# 12V_VMOT_SUPPLY.net
KiCad netlist of a schematic drawn in Altium Designer
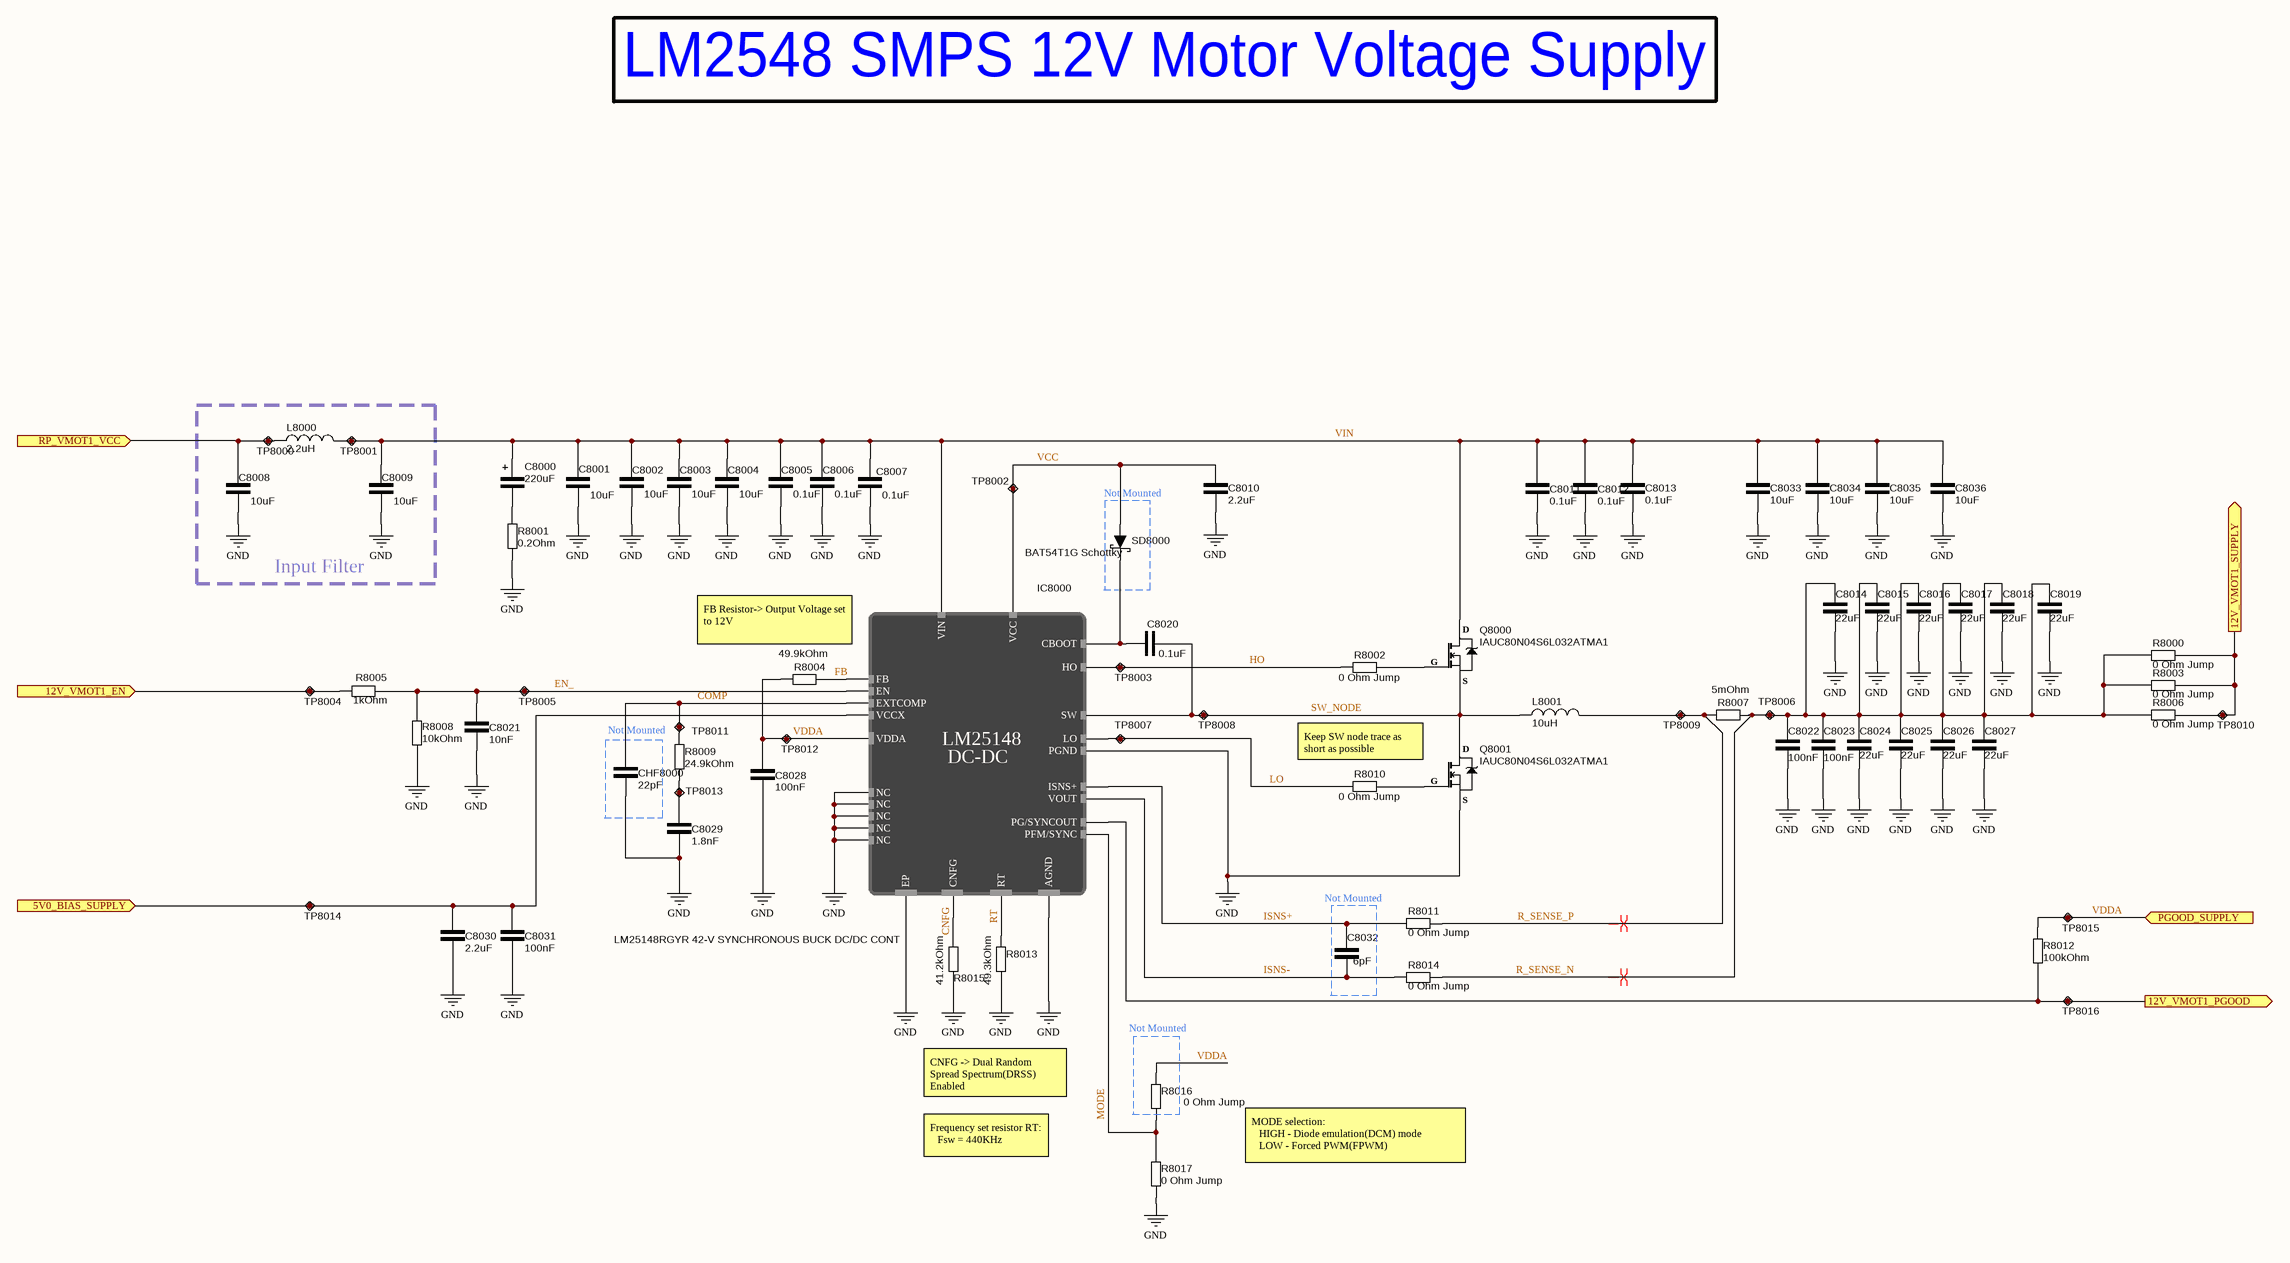
[diagram p0: 12V_VMOT_SUPPLY.SchDoc]

(export (version "E")
  (design (tool "Eeschema 10.0.6"))
  (components
    (comp (ref "C8000")
      (value "220uF")
      (footprint "CAPAE109103X103M")
      (description "220 µF 35 V Aluminum - Polymer Capacitors Radial, Can - SMD 23mOhm 1000 Hrs @ 150°C")
      (fields (field (name "DIGIKEY PART NUMBER") "399-A785MN227M1VLAS023CT-ND"))
      (libsource (lib "CapacitorsIntegrated") (part "C000033"))
    )
    (comp (ref "C8001")
      (value "10uF")
      (footprint "CAP_1206")
      (description "10 µF ±10% 50V Ceramic Capacitor X7R 1206 (3216 Metric)")
      (fields (field (name "DIGIKEY PART NUMBER") "1276-6767-1-ND"))
      (libsource (lib "CapacitorsIntegrated") (part "C000017"))
    )
    (comp (ref "C8002")
      (value "10uF")
      (footprint "CAP_1206")
      (description "10 µF ±10% 50V Ceramic Capacitor X7R 1206 (3216 Metric)")
      (fields (field (name "DIGIKEY PART NUMBER") "1276-6767-1-ND"))
      (libsource (lib "") (part "C000017_1"))
    )
    (comp (ref "C8003")
      (value "10uF")
      (footprint "CAP_1206")
      (description "10 µF ±10% 50V Ceramic Capacitor X7R 1206 (3216 Metric)")
      (fields (field (name "DIGIKEY PART NUMBER") "1276-6767-1-ND"))
      (libsource (lib "") (part "C000017_1"))
    )
    (comp (ref "C8004")
      (value "10uF")
      (footprint "CAP_1206")
      (description "10 µF ±10% 50V Ceramic Capacitor X7R 1206 (3216 Metric)")
      (fields (field (name "DIGIKEY PART NUMBER") "1276-6767-1-ND"))
      (libsource (lib "") (part "C000017_1"))
    )
    (comp (ref "C8005")
      (value "0.1uF")
      (footprint "CAP_0603")
      (description "0.1 µF ±10% 50V Ceramic Capacitor X7R 0603 (1608 Metric)")
      (fields (field (name "DIGIKEY PART NUMBER") "1276-1000-1-ND"))
      (libsource (lib "CapacitorsIntegrated") (part "C000018"))
    )
    (comp (ref "C8006")
      (value "0.1uF")
      (footprint "CAP_0603")
      (description "0.1 µF ±10% 50V Ceramic Capacitor X7R 0603 (1608 Metric)")
      (fields (field (name "DIGIKEY PART NUMBER") "1276-1000-1-ND"))
      (libsource (lib "CapacitorsIntegrated") (part "C000018"))
    )
    (comp (ref "C8007")
      (value "0.1uF")
      (footprint "CAP_0603")
      (description "0.1 µF ±10% 50V Ceramic Capacitor X7R 0603 (1608 Metric)")
      (fields (field (name "DIGIKEY PART NUMBER") "1276-1000-1-ND"))
      (libsource (lib "") (part "C000018_2"))
    )
    (comp (ref "C8008")
      (value "10uF")
      (footprint "CAP_1206")
      (description "10 µF ±10% 50V Ceramic Capacitor X7R 1206 (3216 Metric)")
      (fields (field (name "DIGIKEY PART NUMBER") "1276-6767-1-ND"))
      (libsource (lib "CapacitorsIntegrated") (part "C000017"))
    )
    (comp (ref "C8009")
      (value "10uF")
      (footprint "CAP_1206")
      (description "10 µF ±10% 50V Ceramic Capacitor X7R 1206 (3216 Metric)")
      (fields (field (name "DIGIKEY PART NUMBER") "1276-6767-1-ND"))
      (libsource (lib "CapacitorsIntegrated") (part "C000017"))
    )
    (comp (ref "C8010")
      (value "2.2uF")
      (footprint "CAP_0603")
      (description "8 pF ±0.05pF 25V Ceramic Capacitor C0G, NP0 01005 (0402 Metric)")
      (fields (field (name "DIGIKEY PART NUMBER") "490-12731-1-ND"))
      (libsource (lib "") (part "C000014_1"))
    )
    (comp (ref "C8011")
      (value "0.1uF")
      (footprint "CAP_0603")
      (description "0.1 µF ±10% 50V Ceramic Capacitor X7R 0603 (1608 Metric)")
      (fields (field (name "DIGIKEY PART NUMBER") "1276-1000-1-ND"))
      (libsource (lib "") (part "C000018_2"))
    )
    (comp (ref "C8012")
      (value "0.1uF")
      (footprint "CAP_0603")
      (description "0.1 µF ±10% 50V Ceramic Capacitor X7R 0603 (1608 Metric)")
      (fields (field (name "DIGIKEY PART NUMBER") "1276-1000-1-ND"))
      (libsource (lib "") (part "C000018_2"))
    )
    (comp (ref "C8013")
      (value "0.1uF")
      (footprint "CAP_0603")
      (description "0.1 µF ±10% 50V Ceramic Capacitor X7R 0603 (1608 Metric)")
      (fields (field (name "DIGIKEY PART NUMBER") "1276-1000-1-ND"))
      (libsource (lib "CapacitorsIntegrated") (part "C000018"))
    )
    (comp (ref "C8014")
      (value "22uF")
      (footprint "CAP_1210")
      (description "22 µF ±10% 25V Ceramic Capacitor X7R 1210 (3225 Metric)")
      (fields (field (name "DIGIKEY PART NUMBER") "1276-3392-1-ND"))
      (libsource (lib "") (part "C000032_1"))
    )
    (comp (ref "C8015")
      (value "22uF")
      (footprint "CAP_1210")
      (description "22 µF ±10% 25V Ceramic Capacitor X7R 1210 (3225 Metric)")
      (fields (field (name "DIGIKEY PART NUMBER") "1276-3392-1-ND"))
      (libsource (lib "CapacitorsIntegrated") (part "C000032"))
    )
    (comp (ref "C8016")
      (value "22uF")
      (footprint "CAP_1210")
      (description "22 µF ±10% 25V Ceramic Capacitor X7R 1210 (3225 Metric)")
      (fields (field (name "DIGIKEY PART NUMBER") "1276-3392-1-ND"))
      (libsource (lib "") (part "C000032_1"))
    )
    (comp (ref "C8017")
      (value "22uF")
      (footprint "CAP_1210")
      (description "22 µF ±10% 25V Ceramic Capacitor X7R 1210 (3225 Metric)")
      (fields (field (name "DIGIKEY PART NUMBER") "1276-3392-1-ND"))
      (libsource (lib "") (part "C000032_1"))
    )
    (comp (ref "C8018")
      (value "22uF")
      (footprint "CAP_1210")
      (description "22 µF ±10% 25V Ceramic Capacitor X7R 1210 (3225 Metric)")
      (fields (field (name "DIGIKEY PART NUMBER") "1276-3392-1-ND"))
      (libsource (lib "CapacitorsIntegrated") (part "C000032"))
    )
    (comp (ref "C8019")
      (value "22uF")
      (footprint "CAP_1210")
      (description "22 µF ±10% 25V Ceramic Capacitor X7R 1210 (3225 Metric)")
      (fields (field (name "DIGIKEY PART NUMBER") "1276-3392-1-ND"))
      (libsource (lib "") (part "C000032_1"))
    )
    (comp (ref "C8020")
      (value "0.1uF")
      (footprint "CAP_0603")
      (description "0.1 µF ±10% 50V Ceramic Capacitor X7R 0603 (1608 Metric)")
      (fields (field (name "DIGIKEY PART NUMBER") "1276-1000-1-ND"))
      (libsource (lib "") (part "C000018_1"))
    )
    (comp (ref "C8021")
      (value "10nF")
      (footprint "CAP_0603")
      (description "10000 pF ±20% 25V Ceramic Capacitor X7R 0603 (1608 Metric)")
      (fields (field (name "DIGIKEY PART NUMBER") "478-KGM15AR71E103MTCT-ND"))
      (libsource (lib "CapacitorsIntegrated") (part "C000005"))
    )
    (comp (ref "C8022")
      (value "100nF")
      (footprint "CAP_0603")
      (description "0.1 µF ±10% 25V Ceramic Capacitor X7R 0603 (1608 Metric)")
      (fields (field (name "DIGIKEY PART NUMBER") "478-KAM15AR71E104KTCT-ND"))
      (libsource (lib "CapacitorsIntegrated") (part "C000007"))
    )
    (comp (ref "C8023")
      (value "100nF")
      (footprint "CAP_0603")
      (description "0.1 µF ±10% 25V Ceramic Capacitor X7R 0603 (1608 Metric)")
      (fields (field (name "DIGIKEY PART NUMBER") "478-KAM15AR71E104KTCT-ND"))
      (libsource (lib "CapacitorsIntegrated") (part "C000007"))
    )
    (comp (ref "C8024")
      (value "22uF")
      (footprint "CAP_1210")
      (description "22 µF ±10% 25V Ceramic Capacitor X7R 1210 (3225 Metric)")
      (fields (field (name "DIGIKEY PART NUMBER") "1276-3392-1-ND"))
      (libsource (lib "CapacitorsIntegrated") (part "C000032"))
    )
    (comp (ref "C8025")
      (value "22uF")
      (footprint "CAP_1210")
      (description "22 µF ±10% 25V Ceramic Capacitor X7R 1210 (3225 Metric)")
      (fields (field (name "DIGIKEY PART NUMBER") "1276-3392-1-ND"))
      (libsource (lib "CapacitorsIntegrated") (part "C000032"))
    )
    (comp (ref "C8026")
      (value "22uF")
      (footprint "CAP_1210")
      (description "22 µF ±10% 25V Ceramic Capacitor X7R 1210 (3225 Metric)")
      (fields (field (name "DIGIKEY PART NUMBER") "1276-3392-1-ND"))
      (libsource (lib "") (part "C000032_1"))
    )
    (comp (ref "C8027")
      (value "22uF")
      (footprint "CAP_1210")
      (description "22 µF ±10% 25V Ceramic Capacitor X7R 1210 (3225 Metric)")
      (fields (field (name "DIGIKEY PART NUMBER") "1276-3392-1-ND"))
      (libsource (lib "CapacitorsIntegrated") (part "C000032"))
    )
    (comp (ref "C8028")
      (value "100nF")
      (footprint "CAP_0603")
      (description "0.1 µF ±10% 25V Ceramic Capacitor X7R 0603 (1608 Metric)")
      (fields (field (name "DIGIKEY PART NUMBER") "478-KAM15AR71E104KTCT-ND"))
      (libsource (lib "CapacitorsIntegrated") (part "C000007"))
    )
    (comp (ref "C8029")
      (value "1.8nF")
      (footprint "CAP_0603")
      (description "1800 pF ±10% 25V Ceramic Capacitor X7R 0603 (1608 Metric)")
      (fields (field (name "DIGIKEY PART NUMBER") "399-15370-1-ND"))
      (libsource (lib "CapacitorsIntegrated") (part "C000027"))
    )
    (comp (ref "C8030")
      (value "2.2uF")
      (footprint "CAP_0603")
      (description "8 pF ±0.05pF 25V Ceramic Capacitor C0G, NP0 01005 (0402 Metric)")
      (fields (field (name "DIGIKEY PART NUMBER") "490-12731-1-ND"))
      (libsource (lib "CapacitorsIntegrated") (part "C000014"))
    )
    (comp (ref "C8031")
      (value "100nF")
      (footprint "CAP_0603")
      (description "0.1 µF ±10% 25V Ceramic Capacitor X7R 0603 (1608 Metric)")
      (fields (field (name "DIGIKEY PART NUMBER") "478-KAM15AR71E104KTCT-ND"))
      (libsource (lib "CapacitorsIntegrated") (part "C000007"))
    )
    (comp (ref "C8032")
      (value "6pF")
      (footprint "CAP_0402")
      (description "6 pF ±0.5pF 25V Ceramic Capacitor C0G, NP0 0402 (1005 Metric)")
      (fields (field (name "DIGIKEY PART NUMBER") "399-CBR04C609D3GACCT-ND"))
      (libsource (lib "CapacitorsIntegrated") (part "C000016"))
    )
    (comp (ref "C8033")
      (value "10uF")
      (footprint "CAP_1206")
      (description "10 µF ±10% 50V Ceramic Capacitor X7R 1206 (3216 Metric)")
      (fields (field (name "DIGIKEY PART NUMBER") "1276-6767-1-ND"))
      (libsource (lib "CapacitorsIntegrated") (part "C000017"))
    )
    (comp (ref "C8034")
      (value "10uF")
      (footprint "CAP_1206")
      (description "10 µF ±10% 50V Ceramic Capacitor X7R 1206 (3216 Metric)")
      (fields (field (name "DIGIKEY PART NUMBER") "1276-6767-1-ND"))
      (libsource (lib "CapacitorsIntegrated") (part "C000017"))
    )
    (comp (ref "C8035")
      (value "10uF")
      (footprint "CAP_1206")
      (description "10 µF ±10% 50V Ceramic Capacitor X7R 1206 (3216 Metric)")
      (fields (field (name "DIGIKEY PART NUMBER") "1276-6767-1-ND"))
      (libsource (lib "CapacitorsIntegrated") (part "C000017"))
    )
    (comp (ref "C8036")
      (value "10uF")
      (footprint "CAP_1206")
      (description "10 µF ±10% 50V Ceramic Capacitor X7R 1206 (3216 Metric)")
      (fields (field (name "DIGIKEY PART NUMBER") "1276-6767-1-ND"))
      (libsource (lib "CapacitorsIntegrated") (part "C000017"))
    )
    (comp (ref "CHF8000")
      (value "22pF")
      (footprint "CAP_0603")
      (description "22 pF ±10% 25V Ceramic Capacitor X7R 0603 (1608 Metric)")
      (fields (field (name "DIGIKEY PART NUMBER") "399-C0603C220K3RACAUTOCT-ND"))
      (libsource (lib "CapacitorsIntegrated") (part "C000024"))
    )
    (comp (ref "IC8000")
      (value "LM25148RGYR 42-V SYNCHRONOUS BUCK DC/DC CONT")
      (footprint "VQFN25_RGY_TEX")
      (description "Buck Regulator Positive Output Step-Down DC-DC Controller IC 24-VQFN (5.5x3.5)")
      (fields
        (field (name "DIGIKEY PART NUMBER") "296-LM25148RGYRCT-ND")
        (field (name "MOUSER PART NUMBER") "595-LM25148RGYR")
      )
      (libsource (lib "IntegratedCircuits") (part "LM25148RGYR"))
    )
    (comp (ref "L8000")
      (value "2.2uH")
      (footprint "IHLP-3232DZ-51")
      (description "FIXED IND 2.2UH 11.5A 12.5 MOHM")
      (fields
        (field (name "DIGIKEY PART NUMBER") "541-IHLP3232DZER2R2M5ACT-ND")
        (field (name "MOUSER PART NUMBER") "70-IHLP3232DZR2R2M5A")
      )
      (libsource (lib "InductorIntegrated") (part "L000015"))
    )
    (comp (ref "L8001")
      (value "10uH")
      (footprint "INDP135126X65N")
      (description "FIXED IND 10UH 11A 15.8 MOHM SMD")
      (fields
        (field (name "DIGIKEY PART NUMBER") "553-4029-1-ND")
        (field (name "MOUSER PART NUMBER") "673-PA4343.103ANLT")
      )
      (libsource (lib "InductorIntegrated") (part "L000016"))
    )
    (comp (ref "Q8000")
      (value "IAUC80N04S6L032ATMA1")
      (footprint "PG-TDSON-8-33")
      (description "N-Channel 40 V 80A (Tc) 50W (Tc) Surface Mount PG-TDSON-8")
      (fields
        (field (name "DIGIKEY PART NUMBER") "448-IAUC80N04S6L032ATMA1CT-ND")
        (field (name "MOUSER PART NUMBER") "726-IAUC80N04S6L032A")
      )
      (libsource (lib "Miscellaneous_Lib1") (part "00000008"))
    )
    (comp (ref "Q8001")
      (value "IAUC80N04S6L032ATMA1")
      (footprint "PG-TDSON-8-33")
      (description "N-Channel 40 V 80A (Tc) 50W (Tc) Surface Mount PG-TDSON-8")
      (fields
        (field (name "DIGIKEY PART NUMBER") "448-IAUC80N04S6L032ATMA1CT-ND")
        (field (name "MOUSER PART NUMBER") "726-IAUC80N04S6L032A")
      )
      (libsource (lib "Miscellaneous_Lib1") (part "00000008"))
    )
    (comp (ref "R8000")
      (value "0 Ohm Jump")
      (footprint "RES_1206")
      (description "0 Ohms Jumper Chip Resistor 1206 (3216 Metric) Automotive AEC-Q200 Thick Film")
      (fields (field (name "DIGIKEY PART NUMBER") "RMCF1206ZT0R00CT-ND"))
      (libsource (lib "ResistorsIntegrated") (part "R000012"))
    )
    (comp (ref "R8001")
      (value "0.2Ohm")
      (footprint "RES_1206")
      (description "200 mOhms ±1% 0.5W, 1/2W Chip Resistor 1206 (3216 Metric) Current Sense Thick Film")
      (fields (field (name "DIGIKEY PART NUMBER") "CSR1206FKR200CT-ND"))
      (libsource (lib "ResistorsIntegrated") (part "R000024"))
    )
    (comp (ref "R8002")
      (value "0 Ohm Jump")
      (footprint "RES_0402")
      (description "0 Ohms Jumper Chip Resistor 0402 (1005 Metric) Automotive AEC-Q200 Thick Film")
      (fields (field (name "DIGIKEY PART NUMBER") "P0.0JCT-ND"))
      (libsource (lib "ResistorsIntegrated") (part "R000008"))
    )
    (comp (ref "R8003")
      (value "0 Ohm Jump")
      (footprint "RES_1206")
      (description "0 Ohms Jumper Chip Resistor 1206 (3216 Metric) Automotive AEC-Q200 Thick Film")
      (fields (field (name "DIGIKEY PART NUMBER") "RMCF1206ZT0R00CT-ND"))
      (libsource (lib "ResistorsIntegrated") (part "R000012"))
    )
    (comp (ref "R8004")
      (value "49.9kOhm")
      (footprint "RES_0603")
      (description "49.9 kOhms ±1% 0.1W, 1/10W Chip Resistor 0603 (1608 Metric) Moisture Resistant Thick Film")
      (fields (field (name "DIGIKEY PART NUMBER") "311-49.9KHRCT-ND"))
      (libsource (lib "ResistorsIntegrated") (part "R000025"))
    )
    (comp (ref "R8005")
      (value "1kOhm")
      (footprint "RES_0603")
      (description "1 kOhms ±1% 0.125W, 1/8W Chip Resistor 0603 (1608 Metric) Anti-Sulfur Thin Film")
      (fields (field (name "DIGIKEY PART NUMBER") "MCT0603-1.00K-CFCT-ND"))
      (libsource (lib "ResistorsIntegrated") (part "R000004"))
    )
    (comp (ref "R8006")
      (value "0 Ohm Jump")
      (footprint "RES_1206")
      (description "0 Ohms Jumper Chip Resistor 1206 (3216 Metric) Automotive AEC-Q200 Thick Film")
      (fields (field (name "DIGIKEY PART NUMBER") "RMCF1206ZT0R00CT-ND"))
      (libsource (lib "ResistorsIntegrated") (part "R000012"))
    )
    (comp (ref "R8007")
      (value "5mOhm")
      (footprint "RES_1020_WIDE")
      (fields (field (name "DIGIKEY PART NUMBER") "541-10046-1-ND"))
      (libsource (lib "ResistorsIntegrated") (part "R000026"))
    )
    (comp (ref "R8008")
      (value "10kOhm")
      (footprint "RES_0603")
      (description "10 kOhms ±1% 0.125W, 1/8W Chip Resistor 0603 (1608 Metric) Anti-Sulfur Thin Film")
      (fields (field (name "DIGIKEY PART NUMBER") "MCT0603-10.0K-CFCT-ND"))
      (libsource (lib "ResistorsIntegrated") (part "R000001"))
    )
    (comp (ref "R8009")
      (value "24.9kOhm")
      (footprint "RES_0603")
      (description "24.9 kOhms ±1% 0.1W, 1/10W Chip Resistor 0603 (1608 Metric) Automotive AEC-Q200 Thick Film")
      (fields (field (name "DIGIKEY PART NUMBER") "P24.9KHCT-ND"))
      (libsource (lib "ResistorsIntegrated") (part "R000017"))
    )
    (comp (ref "R8010")
      (value "0 Ohm Jump")
      (footprint "RES_0402")
      (description "0 Ohms Jumper Chip Resistor 0402 (1005 Metric) Automotive AEC-Q200 Thick Film")
      (fields (field (name "DIGIKEY PART NUMBER") "P0.0JCT-ND"))
      (libsource (lib "ResistorsIntegrated") (part "R000008"))
    )
    (comp (ref "R8011")
      (value "0 Ohm Jump")
      (footprint "RES_0402")
      (description "0 Ohms Jumper Chip Resistor 0402 (1005 Metric) Automotive AEC-Q200 Thick Film")
      (fields (field (name "DIGIKEY PART NUMBER") "P0.0JCT-ND"))
      (libsource (lib "ResistorsIntegrated") (part "R000008"))
    )
    (comp (ref "R8012")
      (value "100kOhm")
      (footprint "RES_0603")
      (description "100 kOhms ±1% 0.1W, 1/10W Chip Resistor 0603 (1608 Metric) Automotive AEC-Q200 Thick Film")
      (fields (field (name "DIGIKEY PART NUMBER") "RMCF0603FG100KCT-ND"))
      (libsource (lib "ResistorsIntegrated") (part "R000006"))
    )
    (comp (ref "R8013")
      (value "49.3kOhm")
      (footprint "RES_0603")
      (description "49.3 kOhms ±0.1% 0.1W, 1/10W Chip Resistor 0603 (1608 Metric) Thin Film")
      (fields (field (name "DIGIKEY PART NUMBER") "13-RT0603BRD0749K3LCT-ND"))
      (libsource (lib "ResistorsIntegrated") (part "R000023"))
    )
    (comp (ref "R8014")
      (value "0 Ohm Jump")
      (footprint "RES_0402")
      (description "0 Ohms Jumper Chip Resistor 0402 (1005 Metric) Automotive AEC-Q200 Thick Film")
      (fields (field (name "DIGIKEY PART NUMBER") "P0.0JCT-ND"))
      (libsource (lib "ResistorsIntegrated") (part "R000008"))
    )
    (comp (ref "R8015")
      (value "41.2kOhm")
      (footprint "RES_0603")
      (description "41.2 kOhms ±1% 0.1W, 1/10W Chip Resistor 0603 (1608 Metric) Automotive AEC-Q200 Thick Film")
      (fields (field (name "DIGIKEY PART NUMBER") "P41.2KHCT-ND"))
      (libsource (lib "ResistorsIntegrated") (part "R000015"))
    )
    (comp (ref "R8016")
      (value "0 Ohm Jump")
      (footprint "RES_0603")
      (description "0 Ohms Jumper Chip Resistor 0603 (1608 Metric) Automotive AEC-Q200 Thick Film")
      (fields (field (name "DIGIKEY PART NUMBER") "RMCF0603ZT0R00CT-ND"))
      (libsource (lib "ResistorsIntegrated") (part "R000007"))
    )
    (comp (ref "R8017")
      (value "0 Ohm Jump")
      (footprint "RES_0603")
      (description "0 Ohms Jumper Chip Resistor 0603 (1608 Metric) Automotive AEC-Q200 Thick Film")
      (fields (field (name "DIGIKEY PART NUMBER") "RMCF0603ZT0R00CT-ND"))
      (libsource (lib "ResistorsIntegrated") (part "R000007"))
    )
    (comp (ref "SD8000")
      (value "BAT54T1G Schottky")
      (footprint "SODFL371X135-2N")
      (description "Diode 30 V 200mA Surface Mount SOD-123")
      (fields (field (name "DIGIKEY PART NUMBER") "BAT54T1GOSCT-ND"))
      (libsource (lib "Miscellaneous_Lib1") (part "00000009"))
    )
    (comp (ref "TP8000")
      (value "Test point")
      (footprint "TestPoint")
      (description "Test point 1mm")
      (libsource (lib "IntegratedCircuits") (part "TP002"))
    )
    (comp (ref "TP8001")
      (value "Test point")
      (footprint "TestPoint")
      (description "Test point 1mm")
      (libsource (lib "IntegratedCircuits") (part "TP002"))
    )
    (comp (ref "TP8002")
      (value "Test point")
      (footprint "TestPoint")
      (description "Test point 1mm")
      (libsource (lib "IntegratedCircuits") (part "TP002"))
    )
    (comp (ref "TP8003")
      (value "Test point")
      (footprint "TestPoint")
      (description "Test point 1mm")
      (libsource (lib "IntegratedCircuits") (part "TP002"))
    )
    (comp (ref "TP8004")
      (value "Test point")
      (footprint "TestPoint")
      (description "Test point 1mm")
      (libsource (lib "IntegratedCircuits") (part "TP002"))
    )
    (comp (ref "TP8005")
      (value "Test point")
      (footprint "TestPoint")
      (description "Test point 1mm")
      (libsource (lib "IntegratedCircuits") (part "TP002"))
    )
    (comp (ref "TP8006")
      (value "Test point")
      (footprint "TestPoint")
      (description "Test point 1mm")
      (libsource (lib "IntegratedCircuits") (part "TP002"))
    )
    (comp (ref "TP8007")
      (value "Test point")
      (footprint "TestPoint")
      (description "Test point 1mm")
      (libsource (lib "IntegratedCircuits") (part "TP002"))
    )
    (comp (ref "TP8008")
      (value "Test point")
      (footprint "TestPoint")
      (description "Test point 1mm")
      (libsource (lib "IntegratedCircuits") (part "TP002"))
    )
    (comp (ref "TP8009")
      (value "Test point")
      (footprint "TestPoint")
      (description "Test point 1mm")
      (libsource (lib "IntegratedCircuits") (part "TP002"))
    )
    (comp (ref "TP8010")
      (value "Test point")
      (footprint "TestPoint")
      (description "Test point 1mm")
      (libsource (lib "IntegratedCircuits") (part "TP002"))
    )
    (comp (ref "TP8011")
      (value "Test point")
      (footprint "TestPoint")
      (description "Test point 1mm")
      (libsource (lib "IntegratedCircuits") (part "TP002"))
    )
    (comp (ref "TP8012")
      (value "Test point")
      (footprint "TestPoint")
      (description "Test point 1mm")
      (libsource (lib "IntegratedCircuits") (part "TP002"))
    )
    (comp (ref "TP8013")
      (value "Test point")
      (footprint "TestPoint")
      (description "Test point 1mm")
      (libsource (lib "IntegratedCircuits") (part "TP002"))
    )
    (comp (ref "TP8014")
      (value "Test point")
      (footprint "TestPoint")
      (description "Test point 1mm")
      (libsource (lib "IntegratedCircuits") (part "TP002"))
    )
    (comp (ref "TP8015")
      (value "Test point")
      (footprint "TestPoint")
      (description "Test point 1mm")
      (libsource (lib "IntegratedCircuits") (part "TP002"))
    )
    (comp (ref "TP8016")
      (value "Test point")
      (footprint "TestPoint")
      (description "Test point 1mm")
      (libsource (lib "IntegratedCircuits") (part "TP002"))
    )
  )
  (nets
    (net (code "1") (name "/5V0_BIAS_SUPPLY") (class "Default")
      (node (ref "C8030") (pin "1") (pinfunction "1_1") (pintype "passive"))
      (node (ref "C8031") (pin "2") (pinfunction "2_2") (pintype "passive"))
      (node (ref "IC8000") (pin "16") (pinfunction "VCCX_16") (pintype "passive"))
      (node (ref "TP8014") (pin "1") (pinfunction "1_1") (pintype "passive"))
    )
    (net (code "2") (name "/12V_VMOT1_EN") (class "Default")
      (node (ref "R8005") (pin "1") (pinfunction "1_1") (pintype "passive"))
      (node (ref "TP8004") (pin "1") (pinfunction "1_1") (pintype "passive"))
    )
    (net (code "3") (name "/12V_VMOT1_PGOOD") (class "Default")
      (node (ref "IC8000") (pin "17") (pinfunction "PG/SYNCOUT_17") (pintype "passive"))
      (node (ref "R8012") (pin "1") (pinfunction "1_1") (pintype "passive"))
      (node (ref "TP8016") (pin "1") (pinfunction "1_1") (pintype "passive"))
    )
    (net (code "4") (name "/12V_VMOT1_SUPPLY") (class "Default")
      (node (ref "R8000") (pin "2") (pinfunction "2_2") (pintype "passive"))
      (node (ref "R8003") (pin "2") (pinfunction "2_2") (pintype "passive"))
      (node (ref "R8006") (pin "2") (pinfunction "2_2") (pintype "passive"))
      (node (ref "TP8010") (pin "1") (pinfunction "1_1") (pintype "passive"))
    )
    (net (code "5") (name "/CNFG") (class "Default")
      (node (ref "IC8000") (pin "3") (pinfunction "CNFG_3") (pintype "passive"))
      (node (ref "R8015") (pin "2") (pinfunction "2_2") (pintype "passive"))
    )
    (net (code "6") (name "/COMP") (class "Default")
      (node (ref "CHF8000") (pin "2") (pinfunction "2_2") (pintype "passive"))
      (node (ref "IC8000") (pin "5") (pinfunction "EXTCOMP_5") (pintype "passive"))
      (node (ref "R8009") (pin "2") (pinfunction "2_2") (pintype "passive"))
      (node (ref "TP8011") (pin "1") (pinfunction "1_1") (pintype "passive"))
    )
    (net (code "7") (name "/EN_") (class "Default")
      (node (ref "C8021") (pin "2") (pinfunction "2_2") (pintype "passive"))
      (node (ref "IC8000") (pin "19") (pinfunction "EN_19") (pintype "passive"))
      (node (ref "R8005") (pin "2") (pinfunction "2_2") (pintype "passive"))
      (node (ref "R8008") (pin "2") (pinfunction "2_2") (pintype "passive"))
      (node (ref "TP8005") (pin "1") (pinfunction "1_1") (pintype "passive"))
    )
    (net (code "8") (name "/FB") (class "Default")
      (node (ref "IC8000") (pin "6") (pinfunction "FB_6") (pintype "passive"))
      (node (ref "R8004") (pin "2") (pinfunction "2_2") (pintype "passive"))
    )
    (net (code "9") (name "/HO") (class "Default")
      (node (ref "IC8000") (pin "13") (pinfunction "HO_13") (pintype "passive"))
      (node (ref "R8002") (pin "1") (pinfunction "1_1") (pintype "passive"))
      (node (ref "TP8003") (pin "1") (pinfunction "1_1") (pintype "passive"))
    )
    (net (code "10") (name "/ISNS+") (class "Default")
      (node (ref "C8032") (pin "2") (pinfunction "2_2") (pintype "passive"))
      (node (ref "IC8000") (pin "20") (pinfunction "ISNS+_20") (pintype "passive"))
      (node (ref "R8011") (pin "1") (pinfunction "1_1") (pintype "passive"))
    )
    (net (code "11") (name "/ISNS-") (class "Default")
      (node (ref "C8032") (pin "1") (pinfunction "1_1") (pintype "passive"))
      (node (ref "IC8000") (pin "21") (pinfunction "VOUT_21") (pintype "passive"))
      (node (ref "R8014") (pin "1") (pinfunction "1_1") (pintype "passive"))
    )
    (net (code "12") (name "/LO") (class "Default")
      (node (ref "IC8000") (pin "11") (pinfunction "LO_11") (pintype "passive"))
      (node (ref "R8010") (pin "1") (pinfunction "1_1") (pintype "passive"))
      (node (ref "TP8007") (pin "1") (pinfunction "1_1") (pintype "passive"))
    )
    (net (code "13") (name "/MODE") (class "Default")
      (node (ref "IC8000") (pin "18") (pinfunction "PFM/SYNC_18") (pintype "passive"))
      (node (ref "R8016") (pin "1") (pinfunction "1_1") (pintype "passive"))
      (node (ref "R8017") (pin "2") (pinfunction "2_2") (pintype "passive"))
    )
    (net (code "14") (name "/RP_VMOT1_VCC") (class "Default")
      (node (ref "C8008") (pin "2") (pinfunction "2_2") (pintype "passive"))
      (node (ref "L8000") (pin "1") (pinfunction "1_1") (pintype "passive"))
      (node (ref "TP8000") (pin "1") (pinfunction "1_1") (pintype "passive"))
    )
    (net (code "15") (name "/RT") (class "Default")
      (node (ref "IC8000") (pin "4") (pinfunction "RT_4") (pintype "passive"))
      (node (ref "R8013") (pin "2") (pinfunction "2_2") (pintype "passive"))
    )
    (net (code "16") (name "/R_SENSE_N") (class "Default")
      (node (ref "C8014") (pin "2") (pinfunction "2_2") (pintype "passive"))
      (node (ref "C8015") (pin "1") (pinfunction "1_1") (pintype "passive"))
      (node (ref "C8016") (pin "2") (pinfunction "2_2") (pintype "passive"))
      (node (ref "C8017") (pin "2") (pinfunction "2_2") (pintype "passive"))
      (node (ref "C8018") (pin "1") (pinfunction "1_1") (pintype "passive"))
      (node (ref "C8019") (pin "2") (pinfunction "2_2") (pintype "passive"))
      (node (ref "C8022") (pin "2") (pinfunction "2_2") (pintype "passive"))
      (node (ref "C8023") (pin "2") (pinfunction "2_2") (pintype "passive"))
      (node (ref "C8024") (pin "1") (pinfunction "1_1") (pintype "passive"))
      (node (ref "C8025") (pin "1") (pinfunction "1_1") (pintype "passive"))
      (node (ref "C8026") (pin "2") (pinfunction "2_2") (pintype "passive"))
      (node (ref "C8027") (pin "1") (pinfunction "1_1") (pintype "passive"))
      (node (ref "R8000") (pin "1") (pinfunction "1_1") (pintype "passive"))
      (node (ref "R8003") (pin "1") (pinfunction "1_1") (pintype "passive"))
      (node (ref "R8006") (pin "1") (pinfunction "1_1") (pintype "passive"))
      (node (ref "R8007") (pin "2") (pinfunction "2_2") (pintype "passive"))
      (node (ref "R8014") (pin "2") (pinfunction "2_2") (pintype "passive"))
      (node (ref "TP8006") (pin "1") (pinfunction "1_1") (pintype "passive"))
    )
    (net (code "17") (name "/R_SENSE_P") (class "Default")
      (node (ref "L8001") (pin "2") (pinfunction "2_2") (pintype "passive"))
      (node (ref "R8007") (pin "1") (pinfunction "1_1") (pintype "passive"))
      (node (ref "R8011") (pin "2") (pinfunction "2_2") (pintype "passive"))
      (node (ref "TP8009") (pin "1") (pinfunction "1_1") (pintype "passive"))
    )
    (net (code "18") (name "/SW_NODE") (class "Default")
      (node (ref "C8020") (pin "1") (pinfunction "1_1") (pintype "passive"))
      (node (ref "IC8000") (pin "14") (pinfunction "SW_14") (pintype "passive"))
      (node (ref "L8001") (pin "1") (pinfunction "1_1") (pintype "passive"))
      (node (ref "Q8000") (pin "S") (pinfunction "Source_S") (pintype "passive"))
      (node (ref "Q8001") (pin "D") (pinfunction "Drain_D") (pintype "passive"))
      (node (ref "TP8008") (pin "1") (pinfunction "1_1") (pintype "passive"))
    )
    (net (code "19") (name "/VCC") (class "Default")
      (node (ref "C8010") (pin "2") (pinfunction "2_2") (pintype "passive"))
      (node (ref "IC8000") (pin "9") (pinfunction "VCC_9") (pintype "passive"))
      (node (ref "SD8000") (pin "1") (pinfunction "Anode_1") (pintype "passive"))
      (node (ref "TP8002") (pin "1") (pinfunction "1_1") (pintype "passive"))
    )
    (net (code "20") (name "/VDDA") (class "Default")
      (node (ref "C8028") (pin "2") (pinfunction "2_2") (pintype "passive"))
      (node (ref "IC8000") (pin "8") (pinfunction "VDDA_8") (pintype "passive"))
      (node (ref "R8004") (pin "1") (pinfunction "1_1") (pintype "passive"))
      (node (ref "R8012") (pin "2") (pinfunction "2_2") (pintype "passive"))
      (node (ref "R8016") (pin "2") (pinfunction "2_2") (pintype "passive"))
      (node (ref "TP8012") (pin "1") (pinfunction "1_1") (pintype "passive"))
      (node (ref "TP8015") (pin "1") (pinfunction "1_1") (pintype "passive"))
    )
    (net (code "21") (name "/VIN") (class "Default")
      (node (ref "C8000") (pin "2") (pinfunction "2_2") (pintype "passive"))
      (node (ref "C8001") (pin "2") (pinfunction "2_2") (pintype "passive"))
      (node (ref "C8002") (pin "1") (pinfunction "1_1") (pintype "passive"))
      (node (ref "C8003") (pin "1") (pinfunction "1_1") (pintype "passive"))
      (node (ref "C8004") (pin "1") (pinfunction "1_1") (pintype "passive"))
      (node (ref "C8005") (pin "1") (pinfunction "1_1") (pintype "passive"))
      (node (ref "C8006") (pin "1") (pinfunction "1_1") (pintype "passive"))
      (node (ref "C8007") (pin "2") (pinfunction "2_2") (pintype "passive"))
      (node (ref "C8009") (pin "2") (pinfunction "2_2") (pintype "passive"))
      (node (ref "C8011") (pin "2") (pinfunction "2_2") (pintype "passive"))
      (node (ref "C8012") (pin "2") (pinfunction "2_2") (pintype "passive"))
      (node (ref "C8013") (pin "1") (pinfunction "1_1") (pintype "passive"))
      (node (ref "C8033") (pin "2") (pinfunction "2_2") (pintype "passive"))
      (node (ref "C8034") (pin "2") (pinfunction "2_2") (pintype "passive"))
      (node (ref "C8035") (pin "2") (pinfunction "2_2") (pintype "passive"))
      (node (ref "C8036") (pin "2") (pinfunction "2_2") (pintype "passive"))
      (node (ref "IC8000") (pin "12") (pinfunction "VIN_12") (pintype "passive"))
      (node (ref "L8000") (pin "2") (pinfunction "2_2") (pintype "passive"))
      (node (ref "Q8000") (pin "D") (pinfunction "Drain_D") (pintype "passive"))
      (node (ref "TP8001") (pin "1") (pinfunction "1_1") (pintype "passive"))
    )
    (net (code "22") (name "GND") (class "Default")
      (node (ref "C8001") (pin "1") (pinfunction "1_1") (pintype "passive"))
      (node (ref "C8002") (pin "2") (pinfunction "2_2") (pintype "passive"))
      (node (ref "C8003") (pin "2") (pinfunction "2_2") (pintype "passive"))
      (node (ref "C8004") (pin "2") (pinfunction "2_2") (pintype "passive"))
      (node (ref "C8005") (pin "2") (pinfunction "2_2") (pintype "passive"))
      (node (ref "C8006") (pin "2") (pinfunction "2_2") (pintype "passive"))
      (node (ref "C8007") (pin "1") (pinfunction "1_1") (pintype "passive"))
      (node (ref "C8008") (pin "1") (pinfunction "1_1") (pintype "passive"))
      (node (ref "C8009") (pin "1") (pinfunction "1_1") (pintype "passive"))
      (node (ref "C8010") (pin "1") (pinfunction "1_1") (pintype "passive"))
      (node (ref "C8011") (pin "1") (pinfunction "1_1") (pintype "passive"))
      (node (ref "C8012") (pin "1") (pinfunction "1_1") (pintype "passive"))
      (node (ref "C8013") (pin "2") (pinfunction "2_2") (pintype "passive"))
      (node (ref "C8014") (pin "1") (pinfunction "1_1") (pintype "passive"))
      (node (ref "C8015") (pin "2") (pinfunction "2_2") (pintype "passive"))
      (node (ref "C8016") (pin "1") (pinfunction "1_1") (pintype "passive"))
      (node (ref "C8017") (pin "1") (pinfunction "1_1") (pintype "passive"))
      (node (ref "C8018") (pin "2") (pinfunction "2_2") (pintype "passive"))
      (node (ref "C8019") (pin "1") (pinfunction "1_1") (pintype "passive"))
      (node (ref "C8021") (pin "1") (pinfunction "1_1") (pintype "passive"))
      (node (ref "C8022") (pin "1") (pinfunction "1_1") (pintype "passive"))
      (node (ref "C8023") (pin "1") (pinfunction "1_1") (pintype "passive"))
      (node (ref "C8024") (pin "2") (pinfunction "2_2") (pintype "passive"))
      (node (ref "C8025") (pin "2") (pinfunction "2_2") (pintype "passive"))
      (node (ref "C8026") (pin "1") (pinfunction "1_1") (pintype "passive"))
      (node (ref "C8027") (pin "2") (pinfunction "2_2") (pintype "passive"))
      (node (ref "C8028") (pin "1") (pinfunction "1_1") (pintype "passive"))
      (node (ref "C8029") (pin "1") (pinfunction "1_1") (pintype "passive"))
      (node (ref "C8030") (pin "2") (pinfunction "2_2") (pintype "passive"))
      (node (ref "C8031") (pin "1") (pinfunction "1_1") (pintype "passive"))
      (node (ref "C8033") (pin "1") (pinfunction "1_1") (pintype "passive"))
      (node (ref "C8034") (pin "1") (pinfunction "1_1") (pintype "passive"))
      (node (ref "C8035") (pin "1") (pinfunction "1_1") (pintype "passive"))
      (node (ref "C8036") (pin "1") (pinfunction "1_1") (pintype "passive"))
      (node (ref "CHF8000") (pin "1") (pinfunction "1_1") (pintype "passive"))
      (node (ref "IC8000") (pin "1") (pinfunction "NC_1") (pintype "passive"))
      (node (ref "IC8000") (pin "10") (pinfunction "PGND_10") (pintype "passive"))
      (node (ref "IC8000") (pin "2") (pinfunction "NC_2") (pintype "passive"))
      (node (ref "IC8000") (pin "22") (pinfunction "NC_22") (pintype "passive"))
      (node (ref "IC8000") (pin "23") (pinfunction "NC_23") (pintype "passive"))
      (node (ref "IC8000") (pin "24") (pinfunction "NC_24") (pintype "passive"))
      (node (ref "IC8000") (pin "25") (pinfunction "EP_25") (pintype "passive"))
      (node (ref "IC8000") (pin "7") (pinfunction "AGND_7") (pintype "passive"))
      (node (ref "Q8001") (pin "S") (pinfunction "Source_S") (pintype "passive"))
      (node (ref "R8001") (pin "1") (pinfunction "1_1") (pintype "passive"))
      (node (ref "R8008") (pin "1") (pinfunction "1_1") (pintype "passive"))
      (node (ref "R8013") (pin "1") (pinfunction "1_1") (pintype "passive"))
      (node (ref "R8015") (pin "1") (pinfunction "1_1") (pintype "passive"))
      (node (ref "R8017") (pin "1") (pinfunction "1_1") (pintype "passive"))
    )
    (net (code "23") (name "Net-(C8000-Pad1)") (class "Default")
      (node (ref "C8000") (pin "1") (pinfunction "1_1") (pintype "passive"))
      (node (ref "R8001") (pin "2") (pinfunction "2_2") (pintype "passive"))
    )
    (net (code "24") (name "Net-(C8029-Pad2)") (class "Default")
      (node (ref "C8029") (pin "2") (pinfunction "2_2") (pintype "passive"))
      (node (ref "R8009") (pin "1") (pinfunction "1_1") (pintype "passive"))
      (node (ref "TP8013") (pin "1") (pinfunction "1_1") (pintype "passive"))
    )
    (net (code "25") (name "Net-(IC8000-CBOOT)") (class "Default")
      (node (ref "C8020") (pin "2") (pinfunction "2_2") (pintype "passive"))
      (node (ref "IC8000") (pin "15") (pinfunction "CBOOT_15") (pintype "passive"))
      (node (ref "SD8000") (pin "2") (pinfunction "Cathode_2") (pintype "passive"))
    )
    (net (code "26") (name "Net-(Q8000-Gate)") (class "Default")
      (node (ref "Q8000") (pin "G") (pinfunction "Gate_G") (pintype "passive"))
      (node (ref "R8002") (pin "2") (pinfunction "2_2") (pintype "passive"))
    )
    (net (code "27") (name "Net-(Q8001-Gate)") (class "Default")
      (node (ref "Q8001") (pin "G") (pinfunction "Gate_G") (pintype "passive"))
      (node (ref "R8010") (pin "2") (pinfunction "2_2") (pintype "passive"))
    )
  )
)
